# Sheet1.net
KiCad netlist of a schematic drawn in Altium Designer
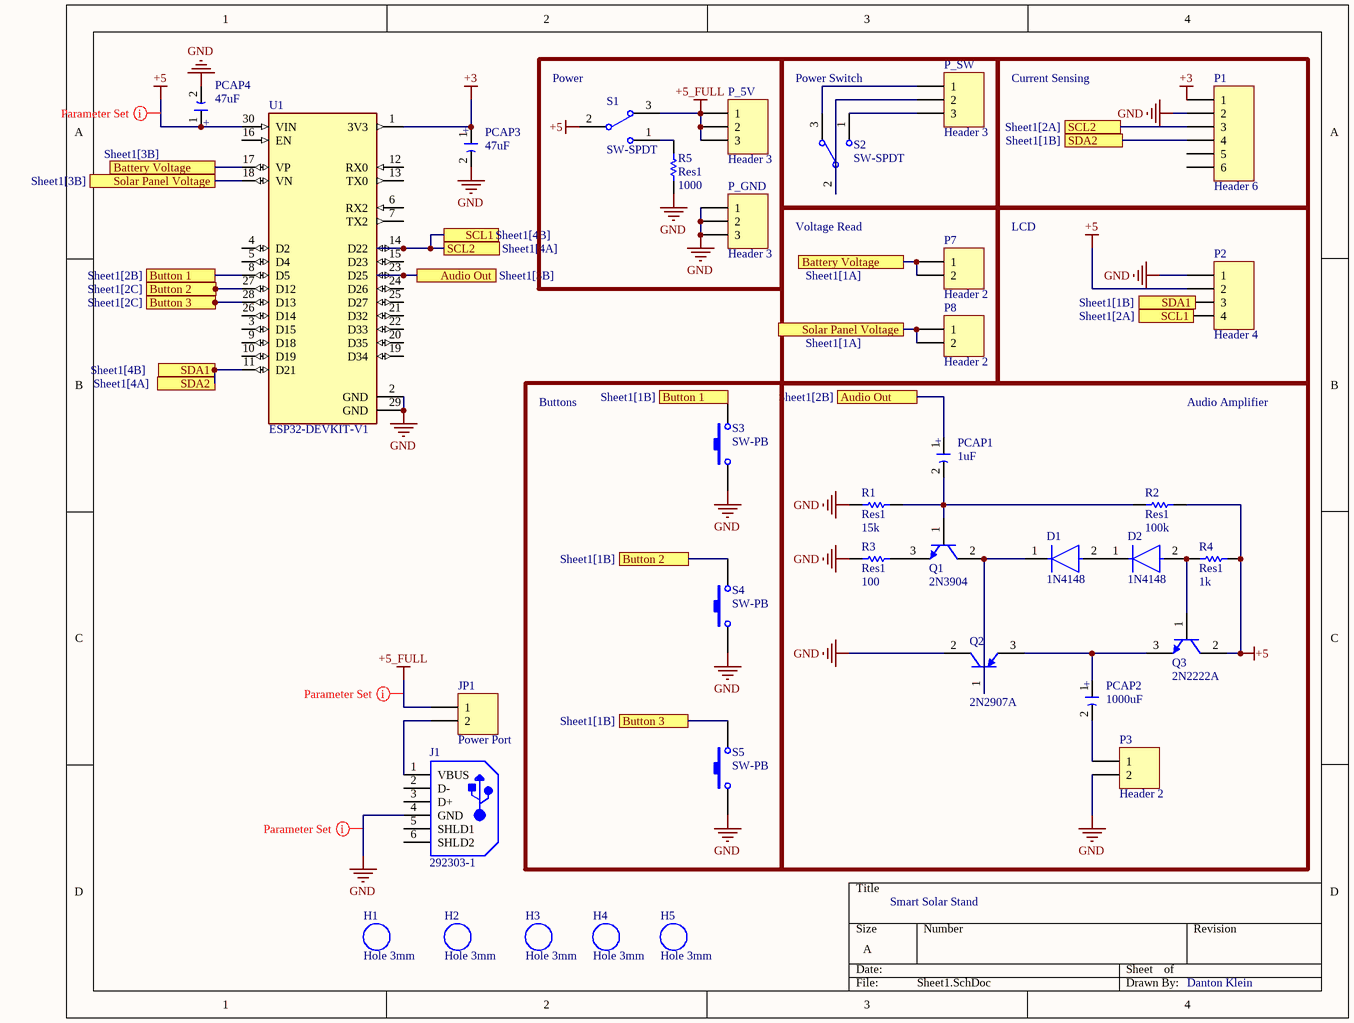
[diagram p0: Sheet1.SchDoc]

(export (version "E")
  (design (tool "Eeschema 10.0.6"))
  (components
    (comp (ref "D1")
      (value "1N4148")
      (footprint "FP-017AG-MFG")
      (description "DIODE GEN PURP 100V 200MA DO35")
      (fields (field (name "VOLTAGE") "100V"))
      (libsource (lib "Altium Content Vault") (part "d7152d700b627762746794eb795d46e"))
    )
    (comp (ref "D2")
      (value "1N4148")
      (footprint "FP-017AG-MFG")
      (description "DIODE GEN PURP 100V 200MA DO35")
      (fields (field (name "VOLTAGE") "100V"))
      (libsource (lib "Altium Content Vault") (part "d7152d700b627762746794eb795d46e"))
    )
    (comp (ref "H1")
      (value "Hole 3mm")
      (footprint "Hole 3mm")
      (libsource (lib "ECE LIB 21") (part "Hole 3mm"))
    )
    (comp (ref "H2")
      (value "Hole 3mm")
      (footprint "Hole 3mm")
      (libsource (lib "ECE LIB 21") (part "Hole 3mm"))
    )
    (comp (ref "H3")
      (value "Hole 3mm")
      (footprint "Hole 3mm")
      (libsource (lib "ECE LIB 21") (part "Hole 3mm"))
    )
    (comp (ref "H4")
      (value "Hole 3mm")
      (footprint "Hole 3mm")
      (libsource (lib "ECE LIB 21") (part "Hole 3mm"))
    )
    (comp (ref "H5")
      (value "Hole 3mm")
      (footprint "Hole 3mm")
      (libsource (lib "ECE LIB 21") (part "Hole 3mm"))
    )
    (comp (ref "J1")
      (value "292303-1")
      (footprint "TE-292303-1_V")
      (fields (field (name "MANUFACTURER") "TE Connectivity"))
      (libsource (lib "Altium Content Vault") (part "USB-4-2SHLD"))
    )
    (comp (ref "JP1")
      (value "Power Port")
      (footprint "CON2screw")
      (libsource (lib "ECE LIB 21") (part "Power"))
    )
    (comp (ref "P1")
      (value "Header 6")
      (footprint "HDR1X6")
      (description "Header, 6-Pin")
      (fields (field (name "PUBLISHER") "Altium Limited"))
      (libsource (lib "Miscellaneous Connectors") (part "Header 6"))
    )
    (comp (ref "P2")
      (value "Header 4")
      (footprint "HDR1X4")
      (description "Header, 4-Pin")
      (fields (field (name "PUBLISHER") "Altium Limited"))
      (libsource (lib "Miscellaneous Connectors") (part "Header 4"))
    )
    (comp (ref "P3")
      (value "Header 2")
      (footprint "HDR1X2")
      (description "Header, 2-Pin")
      (fields (field (name "PUBLISHER") "Altium Limited"))
      (libsource (lib "Miscellaneous Connectors") (part "Header 2"))
    )
    (comp (ref "P7")
      (value "Header 2")
      (footprint "HDR1X2")
      (description "Header, 2-Pin")
      (fields (field (name "PUBLISHER") "Altium Limited"))
      (libsource (lib "Miscellaneous Connectors") (part "Header 2"))
    )
    (comp (ref "P8")
      (value "Header 2")
      (footprint "HDR1X2")
      (description "Header, 2-Pin")
      (fields (field (name "PUBLISHER") "Altium Limited"))
      (libsource (lib "Miscellaneous Connectors") (part "Header 2"))
    )
    (comp (ref "PCAP1")
      (value "1uF")
      (footprint "P Cap - Small")
      (libsource (lib "Custom_Schematics") (part "P Cap"))
    )
    (comp (ref "PCAP2")
      (value "1000uF")
      (footprint "P Cap - Small")
      (libsource (lib "Custom_Schematics") (part "P Cap"))
    )
    (comp (ref "PCAP3")
      (value "47uF")
      (footprint "P Cap - Small")
      (libsource (lib "Custom_Schematics") (part "P Cap"))
    )
    (comp (ref "PCAP4")
      (value "47uF")
      (footprint "P Cap - Small")
      (libsource (lib "Custom_Schematics") (part "P Cap"))
    )
    (comp (ref "P_5V")
      (value "Header 3")
      (footprint "HDR1X3")
      (description "Header, 3-Pin")
      (fields (field (name "PUBLISHER") "Altium Limited"))
      (libsource (lib "Miscellaneous Connectors") (part "Header 3"))
    )
    (comp (ref "P_GND")
      (value "Header 3")
      (footprint "HDR1X3")
      (description "Header, 3-Pin")
      (fields (field (name "PUBLISHER") "Altium Limited"))
      (libsource (lib "Miscellaneous Connectors") (part "Header 3"))
    )
    (comp (ref "P_SW")
      (value "Header 3")
      (footprint "HDR1X3")
      (description "Header, 3-Pin")
      (fields (field (name "PUBLISHER") "Altium Limited"))
      (libsource (lib "Miscellaneous Connectors") (part "Header 3"))
    )
    (comp (ref "Q1")
      (value "2N3904")
      (footprint "STM-TO-18-3")
      (description "High Speed Switch, 0.6 A IC, -65 to 175 degC, 3-Pin TO-18, RoHS, Bulk")
      (fields (field (name "MANUFACTURER") "STMicroelectronics"))
      (libsource (lib "Altium Content Vault") (part "NPN_B1C2E3-3"))
    )
    (comp (ref "Q2")
      (value "2N2907A")
      (footprint "STM-TO-18-3")
      (description "Small Signal PNP Transistor, 0.4 W, 60 V, 600 mA, 3-Pin TO-18, RoHS, Bulk")
      (fields (field (name "MANUFACTURER") "STMicroelectronics"))
      (libsource (lib "Altium Content Vault") (part "BJT-PNP-BCE-3"))
    )
    (comp (ref "Q3")
      (value "2N2222A")
      (footprint "STM-TO-18-3")
      (description "High Speed Switch, 0.6 A IC, -65 to 175 degC, 3-Pin TO-18, RoHS, Bulk")
      (fields (field (name "MANUFACTURER") "STMicroelectronics"))
      (libsource (lib "Altium Content Vault") (part "NPN_B1C2E3-3"))
    )
    (comp (ref "R1")
      (value "Res1")
      (footprint "AXIAL-0.3")
      (description "Resistor")
      (fields (field (name "ALTIUM_VALUE") "15k") (field (name "PUBLISHER") "Altium Limited"))
      (libsource (lib "Miscellaneous Devices") (part "Res1"))
    )
    (comp (ref "R2")
      (value "Res1")
      (footprint "AXIAL-0.3")
      (description "Resistor")
      (fields (field (name "ALTIUM_VALUE") "100k") (field (name "PUBLISHER") "Altium Limited"))
      (libsource (lib "Miscellaneous Devices") (part "Res1"))
    )
    (comp (ref "R3")
      (value "Res1")
      (footprint "AXIAL-0.3")
      (description "Resistor")
      (fields (field (name "ALTIUM_VALUE") "100") (field (name "PUBLISHER") "Altium Limited"))
      (libsource (lib "Miscellaneous Devices") (part "Res1"))
    )
    (comp (ref "R4")
      (value "Res1")
      (footprint "AXIAL-0.3")
      (description "Resistor")
      (fields (field (name "ALTIUM_VALUE") "1k") (field (name "PUBLISHER") "Altium Limited"))
      (libsource (lib "Miscellaneous Devices") (part "Res1"))
    )
    (comp (ref "R5")
      (value "Res1")
      (footprint "AXIAL-0.3")
      (description "Resistor")
      (fields (field (name "ALTIUM_VALUE") "1000") (field (name "PUBLISHER") "Altium Limited"))
      (libsource (lib "Miscellaneous Devices") (part "Res1"))
    )
    (comp (ref "S1")
      (value "SW-SPDT")
      (footprint "SW DPST jameco")
      (description "SPDT Subminiature Toggle Switch, Right Angle Mounting, Vertical Actuation")
      (fields (field (name "PUBLISHER") "Altium Limited"))
      (libsource (lib "ECE LIB new") (part "SW-SPDT"))
    )
    (comp (ref "S2")
      (value "SW-SPDT")
      (footprint "SW DPST jameco")
      (description "SPDT Subminiature Toggle Switch, Right Angle Mounting, Vertical Actuation")
      (fields (field (name "PUBLISHER") "Altium Limited"))
      (libsource (lib "ECE LIB new") (part "SW-SPDT"))
    )
    (comp (ref "S3")
      (value "SW-PB")
      (footprint "SW PB")
      (description "DIGIKEY SW400-ND")
      (fields (field (name "PUBLISHER") "Altium Limited"))
      (libsource (lib "ECE Lib 22") (part "SW-PB"))
    )
    (comp (ref "S4")
      (value "SW-PB")
      (footprint "SW PB")
      (description "DIGIKEY SW400-ND")
      (fields (field (name "PUBLISHER") "Altium Limited"))
      (libsource (lib "ECE Lib 22") (part "SW-PB"))
    )
    (comp (ref "S5")
      (value "SW-PB")
      (footprint "SW PB")
      (description "DIGIKEY SW400-ND")
      (fields (field (name "PUBLISHER") "Altium Limited"))
      (libsource (lib "ECE Lib 22") (part "SW-PB"))
    )
    (comp (ref "U1")
      (value "ESP32-DEVKIT-V1")
      (footprint "MODULE_ESP32_DEVKIT_V1_NOKEEPOUT")
      (fields (field (name "MF") "Do it"))
      (libsource (lib "ESP32-DEVKIT-V1") (part "ESP32-DEVKIT-V1"))
    )
  )
  (nets
    (net (code "1") (name "+3") (class "Default")
      (node (ref "P1") (pin "1") (pinfunction "1_1") (pintype "passive"))
      (node (ref "PCAP3") (pin "1") (pinfunction "1_1") (pintype "passive"))
      (node (ref "U1") (pin "1") (pinfunction "3V3_1") (pintype "output"))
    )
    (net (code "2") (name "+5") (class "Default")
      (node (ref "P2") (pin "2") (pinfunction "2_2") (pintype "passive"))
      (node (ref "PCAP4") (pin "1") (pinfunction "1_1") (pintype "passive"))
      (node (ref "Q3") (pin "2") (pinfunction "C_2") (pintype "passive"))
      (node (ref "R2") (pin "2") (pinfunction "2_2") (pintype "passive"))
      (node (ref "R4") (pin "2") (pinfunction "2_2") (pintype "passive"))
      (node (ref "S1") (pin "2") (pinfunction "2_2") (pintype "passive"))
      (node (ref "U1") (pin "30") (pinfunction "VIN_30") (pintype "input"))
    )
    (net (code "3") (name "+5_FULL") (class "Default")
      (node (ref "JP1") (pin "1") (pinfunction "1_1") (pintype "passive"))
      (node (ref "P_5V") (pin "1") (pinfunction "1_1") (pintype "passive"))
      (node (ref "P_5V") (pin "2") (pinfunction "2_2") (pintype "passive"))
      (node (ref "P_5V") (pin "3") (pinfunction "3_3") (pintype "passive"))
      (node (ref "S1") (pin "3") (pinfunction "3_3") (pintype "passive"))
    )
    (net (code "4") (name "/Audio Out") (class "Default")
      (node (ref "PCAP1") (pin "1") (pinfunction "1_1") (pintype "passive"))
      (node (ref "U1") (pin "23") (pinfunction "D25_23") (pintype "bidirectional"))
    )
    (net (code "5") (name "/Battery Voltage") (class "Default")
      (node (ref "P7") (pin "1") (pinfunction "1_1") (pintype "passive"))
      (node (ref "P7") (pin "2") (pinfunction "2_2") (pintype "passive"))
      (node (ref "U1") (pin "17") (pinfunction "VP_17") (pintype "bidirectional"))
    )
    (net (code "6") (name "/Button 1") (class "Default")
      (node (ref "S3") (pin "2") (pinfunction "2_2") (pintype "passive"))
      (node (ref "U1") (pin "8") (pinfunction "D5_8") (pintype "bidirectional"))
    )
    (net (code "7") (name "/Button 2") (class "Default")
      (node (ref "S4") (pin "2") (pinfunction "2_2") (pintype "passive"))
      (node (ref "U1") (pin "27") (pinfunction "D12_27") (pintype "bidirectional"))
    )
    (net (code "8") (name "/Button 3") (class "Default")
      (node (ref "S5") (pin "2") (pinfunction "2_2") (pintype "passive"))
      (node (ref "U1") (pin "28") (pinfunction "D13_28") (pintype "bidirectional"))
    )
    (net (code "9") (name "/SCL1") (class "Default")
      (node (ref "P1") (pin "3") (pinfunction "3_3") (pintype "passive"))
      (node (ref "U1") (pin "14") (pinfunction "D22_14") (pintype "bidirectional"))
    )
    (net (code "10") (name "/SDA1") (class "Default")
      (node (ref "P1") (pin "4") (pinfunction "4_4") (pintype "passive"))
      (node (ref "U1") (pin "11") (pinfunction "D21_11") (pintype "bidirectional"))
    )
    (net (code "11") (name "/Solar Panel Voltage") (class "Default")
      (node (ref "P8") (pin "1") (pinfunction "1_1") (pintype "passive"))
      (node (ref "P8") (pin "2") (pinfunction "2_2") (pintype "passive"))
      (node (ref "U1") (pin "18") (pinfunction "VN_18") (pintype "bidirectional"))
    )
    (net (code "12") (name "GND") (class "Default")
      (node (ref "J1") (pin "4") (pinfunction "GND_4") (pintype "passive"))
      (node (ref "P1") (pin "2") (pinfunction "2_2") (pintype "passive"))
      (node (ref "P2") (pin "1") (pinfunction "1_1") (pintype "passive"))
      (node (ref "P3") (pin "2") (pinfunction "2_2") (pintype "passive"))
      (node (ref "PCAP3") (pin "2") (pinfunction "2_2") (pintype "passive"))
      (node (ref "PCAP4") (pin "2") (pinfunction "2_2") (pintype "passive"))
      (node (ref "P_GND") (pin "1") (pinfunction "1_1") (pintype "passive"))
      (node (ref "P_GND") (pin "2") (pinfunction "2_2") (pintype "passive"))
      (node (ref "P_GND") (pin "3") (pinfunction "3_3") (pintype "passive"))
      (node (ref "Q2") (pin "2") (pinfunction "C_2") (pintype "passive"))
      (node (ref "R1") (pin "1") (pinfunction "1_1") (pintype "passive"))
      (node (ref "R3") (pin "1") (pinfunction "1_1") (pintype "passive"))
      (node (ref "R5") (pin "1") (pinfunction "1_1") (pintype "passive"))
      (node (ref "S3") (pin "1") (pinfunction "1_1") (pintype "passive"))
      (node (ref "S4") (pin "1") (pinfunction "1_1") (pintype "passive"))
      (node (ref "S5") (pin "1") (pinfunction "1_1") (pintype "passive"))
      (node (ref "U1") (pin "2") (pinfunction "GND_2") (pintype "power_in"))
      (node (ref "U1") (pin "29") (pinfunction "GND_29") (pintype "power_in"))
    )
    (net (code "13") (name "Net-(D1-A)") (class "Default")
      (node (ref "D1") (pin "2") (pinfunction "A_2") (pintype "passive"))
      (node (ref "D2") (pin "1") (pinfunction "C_1") (pintype "passive"))
    )
    (net (code "14") (name "Net-(D1-C)") (class "Default")
      (node (ref "D1") (pin "1") (pinfunction "C_1") (pintype "passive"))
      (node (ref "Q1") (pin "2") (pinfunction "C_2") (pintype "passive"))
      (node (ref "Q2") (pin "1") (pinfunction "B_1") (pintype "passive"))
    )
    (net (code "15") (name "Net-(D2-A)") (class "Default")
      (node (ref "D2") (pin "2") (pinfunction "A_2") (pintype "passive"))
      (node (ref "Q3") (pin "1") (pinfunction "B_1") (pintype "passive"))
      (node (ref "R4") (pin "1") (pinfunction "1_1") (pintype "passive"))
    )
    (net (code "16") (name "Net-(J1-VBUS)") (class "Default")
      (node (ref "J1") (pin "1") (pinfunction "VBUS_1") (pintype "passive"))
      (node (ref "JP1") (pin "2") (pinfunction "2_2") (pintype "passive"))
    )
    (net (code "17") (name "Net-(P3-Pad1)") (class "Default")
      (node (ref "P3") (pin "1") (pinfunction "1_1") (pintype "passive"))
      (node (ref "PCAP2") (pin "2") (pinfunction "2_2") (pintype "passive"))
    )
    (net (code "18") (name "Net-(P_SW-Pad1)") (class "Default")
      (node (ref "P_SW") (pin "1") (pinfunction "1_1") (pintype "passive"))
      (node (ref "S2") (pin "3") (pinfunction "3_3") (pintype "passive"))
    )
    (net (code "19") (name "Net-(P_SW-Pad2)") (class "Default")
      (node (ref "P_SW") (pin "2") (pinfunction "2_2") (pintype "passive"))
      (node (ref "S2") (pin "2") (pinfunction "2_2") (pintype "passive"))
    )
    (net (code "20") (name "Net-(P_SW-Pad3)") (class "Default")
      (node (ref "P_SW") (pin "3") (pinfunction "3_3") (pintype "passive"))
      (node (ref "S2") (pin "1") (pinfunction "1_1") (pintype "passive"))
    )
    (net (code "21") (name "Net-(Q1-B)") (class "Default")
      (node (ref "PCAP1") (pin "2") (pinfunction "2_2") (pintype "passive"))
      (node (ref "Q1") (pin "1") (pinfunction "B_1") (pintype "passive"))
      (node (ref "R1") (pin "2") (pinfunction "2_2") (pintype "passive"))
      (node (ref "R2") (pin "1") (pinfunction "1_1") (pintype "passive"))
    )
    (net (code "22") (name "Net-(Q1-E)") (class "Default")
      (node (ref "Q1") (pin "3") (pinfunction "E_3") (pintype "passive"))
      (node (ref "R3") (pin "2") (pinfunction "2_2") (pintype "passive"))
    )
    (net (code "23") (name "Net-(Q2-E)") (class "Default")
      (node (ref "PCAP2") (pin "1") (pinfunction "1_1") (pintype "passive"))
      (node (ref "Q2") (pin "3") (pinfunction "E_3") (pintype "passive"))
      (node (ref "Q3") (pin "3") (pinfunction "E_3") (pintype "passive"))
    )
    (net (code "24") (name "Net-(R5-Pad2)") (class "Default")
      (node (ref "R5") (pin "2") (pinfunction "2_2") (pintype "passive"))
      (node (ref "S1") (pin "1") (pinfunction "1_1") (pintype "passive"))
    )
    (net (code "25") (name "unconnected-(J1-D+-Pad3)") (class "Default")
      (node (ref "J1") (pin "3") (pinfunction "D+_3") (pintype "passive"))
    )
    (net (code "26") (name "unconnected-(J1-D--Pad2)") (class "Default")
      (node (ref "J1") (pin "2") (pinfunction "D-_2") (pintype "passive"))
    )
    (net (code "27") (name "unconnected-(J1-SHLD1-Pad5)") (class "Default")
      (node (ref "J1") (pin "5") (pinfunction "SHLD1_5") (pintype "passive"))
    )
    (net (code "28") (name "unconnected-(J1-SHLD2-Pad6)") (class "Default")
      (node (ref "J1") (pin "6") (pinfunction "SHLD2_6") (pintype "passive"))
    )
    (net (code "29") (name "unconnected-(P1-Pad5)") (class "Default")
      (node (ref "P1") (pin "5") (pinfunction "5_5") (pintype "passive"))
    )
    (net (code "30") (name "unconnected-(P1-Pad6)") (class "Default")
      (node (ref "P1") (pin "6") (pinfunction "6_6") (pintype "passive"))
    )
    (net (code "31") (name "unconnected-(P2-Pad3)") (class "Default")
      (node (ref "P2") (pin "3") (pinfunction "3_3") (pintype "passive"))
    )
    (net (code "32") (name "unconnected-(P2-Pad4)") (class "Default")
      (node (ref "P2") (pin "4") (pinfunction "4_4") (pintype "passive"))
    )
    (net (code "33") (name "unconnected-(U1-D2-Pad4)") (class "Default")
      (node (ref "U1") (pin "4") (pinfunction "D2_4") (pintype "bidirectional"))
    )
    (net (code "34") (name "unconnected-(U1-D4-Pad5)") (class "Default")
      (node (ref "U1") (pin "5") (pinfunction "D4_5") (pintype "bidirectional"))
    )
    (net (code "35") (name "unconnected-(U1-D14-Pad26)") (class "Default")
      (node (ref "U1") (pin "26") (pinfunction "D14_26") (pintype "bidirectional"))
    )
    (net (code "36") (name "unconnected-(U1-D15-Pad3)") (class "Default")
      (node (ref "U1") (pin "3") (pinfunction "D15_3") (pintype "bidirectional"))
    )
    (net (code "37") (name "unconnected-(U1-D18-Pad9)") (class "Default")
      (node (ref "U1") (pin "9") (pinfunction "D18_9") (pintype "bidirectional"))
    )
    (net (code "38") (name "unconnected-(U1-D19-Pad10)") (class "Default")
      (node (ref "U1") (pin "10") (pinfunction "D19_10") (pintype "bidirectional"))
    )
    (net (code "39") (name "unconnected-(U1-D23-Pad15)") (class "Default")
      (node (ref "U1") (pin "15") (pinfunction "D23_15") (pintype "bidirectional"))
    )
    (net (code "40") (name "unconnected-(U1-D26-Pad24)") (class "Default")
      (node (ref "U1") (pin "24") (pinfunction "D26_24") (pintype "bidirectional"))
    )
    (net (code "41") (name "unconnected-(U1-D27-Pad25)") (class "Default")
      (node (ref "U1") (pin "25") (pinfunction "D27_25") (pintype "bidirectional"))
    )
    (net (code "42") (name "unconnected-(U1-D32-Pad21)") (class "Default")
      (node (ref "U1") (pin "21") (pinfunction "D32_21") (pintype "bidirectional"))
    )
    (net (code "43") (name "unconnected-(U1-D33-Pad22)") (class "Default")
      (node (ref "U1") (pin "22") (pinfunction "D33_22") (pintype "bidirectional"))
    )
    (net (code "44") (name "unconnected-(U1-D34-Pad19)") (class "Default")
      (node (ref "U1") (pin "19") (pinfunction "D34_19") (pintype "bidirectional"))
    )
    (net (code "45") (name "unconnected-(U1-D35-Pad20)") (class "Default")
      (node (ref "U1") (pin "20") (pinfunction "D35_20") (pintype "bidirectional"))
    )
    (net (code "46") (name "unconnected-(U1-EN-Pad16)") (class "Default")
      (node (ref "U1") (pin "16") (pinfunction "EN_16") (pintype "input"))
    )
    (net (code "47") (name "unconnected-(U1-RX0-Pad12)") (class "Default")
      (node (ref "U1") (pin "12") (pinfunction "RX0_12") (pintype "input"))
    )
    (net (code "48") (name "unconnected-(U1-RX2-Pad6)") (class "Default")
      (node (ref "U1") (pin "6") (pinfunction "RX2_6") (pintype "input"))
    )
    (net (code "49") (name "unconnected-(U1-TX0-Pad13)") (class "Default")
      (node (ref "U1") (pin "13") (pinfunction "TX0_13") (pintype "output"))
    )
    (net (code "50") (name "unconnected-(U1-TX2-Pad7)") (class "Default")
      (node (ref "U1") (pin "7") (pinfunction "TX2_7") (pintype "output"))
    )
  )
)
